# Kodi_Remote.net
KiCad netlist of a schematic drawn in EAGLE
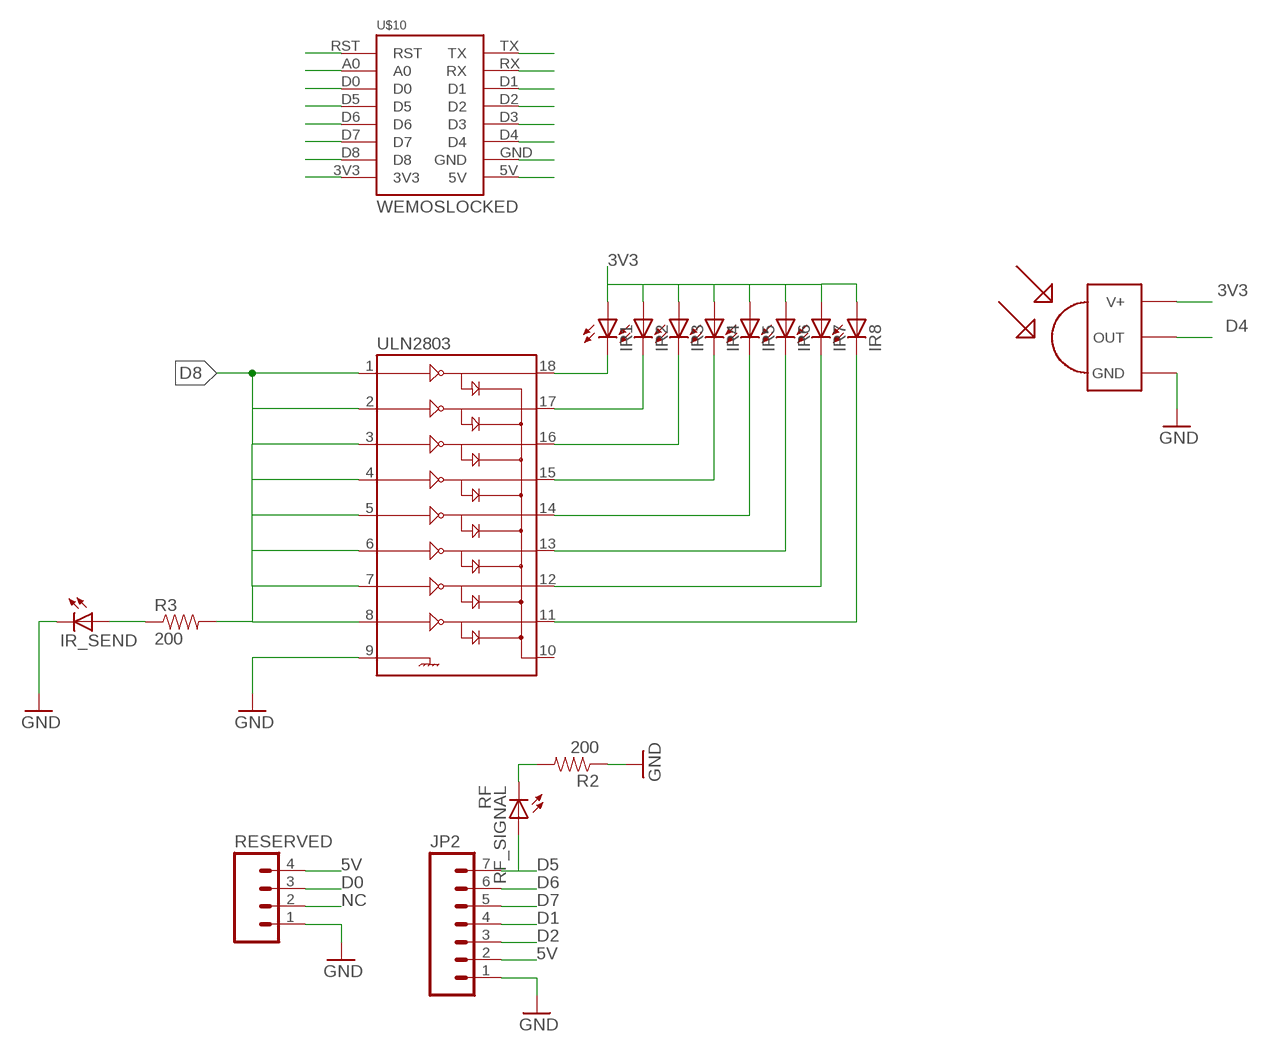
[diagram p0: schematic, sheet 1]

(export (version "E")
  (design (tool "Eeschema 10.0.6"))
  (components
    (comp (ref "IR1")
      (value "LED5MM")
      (footprint "eagle-import:LED5MM")
      (libsource (lib "eagle-import") (part "LED5MM"))
    )
    (comp (ref "IR2")
      (value "LED5MM")
      (footprint "eagle-import:LED5MM")
      (libsource (lib "eagle-import") (part "LED5MM"))
    )
    (comp (ref "IR3")
      (value "LED5MM")
      (footprint "eagle-import:LED5MM")
      (libsource (lib "eagle-import") (part "LED5MM"))
    )
    (comp (ref "IR4")
      (value "LED5MM")
      (footprint "eagle-import:LED5MM")
      (libsource (lib "eagle-import") (part "LED5MM"))
    )
    (comp (ref "IR5")
      (value "LED5MM")
      (footprint "eagle-import:LED5MM")
      (libsource (lib "eagle-import") (part "LED5MM"))
    )
    (comp (ref "IR6")
      (value "LED5MM")
      (footprint "eagle-import:LED5MM")
      (libsource (lib "eagle-import") (part "LED5MM"))
    )
    (comp (ref "IR7")
      (value "LED5MM")
      (footprint "eagle-import:LED5MM")
      (libsource (lib "eagle-import") (part "LED5MM"))
    )
    (comp (ref "IR8")
      (value "LED5MM")
      (footprint "eagle-import:LED5MM")
      (libsource (lib "eagle-import") (part "LED5MM"))
    )
    (comp (ref "IR_SEND")
      (value "LED3MM")
      (footprint "eagle-import:LED3MM")
      (libsource (lib "eagle-import") (part "LED3MM"))
    )
    (comp (ref "JP2")
      (value "M07")
      (footprint "eagle-import:1X07")
      (libsource (lib "eagle-import") (part "M07"))
    )
    (comp (ref "R2")
      (value "200")
      (footprint "eagle-import:0805")
      (libsource (lib "eagle-import") (part "RESISTOR0805-RES"))
    )
    (comp (ref "R3")
      (value "200")
      (footprint "eagle-import:0805")
      (libsource (lib "eagle-import") (part "RESISTOR0805-RES"))
    )
    (comp (ref "RESERVED")
      (value "M04PTH")
      (footprint "eagle-import:1X04")
      (libsource (lib "eagle-import") (part "M04PTH"))
    )
    (comp (ref "RF_SIGNAL")
      (value "RF")
      (footprint "eagle-import:LED3MM")
      (libsource (lib "eagle-import") (part "LED3MM"))
    )
    (comp (ref "TSOP1838")
      (value "TSOP1838")
      (footprint "eagle-import:TSOP18XX")
      (libsource (lib "eagle-import") (part "TSOP1838"))
    )
    (comp (ref "U$10")
      (value "WEMOSLOCKED")
      (footprint "eagle-import:WEMOS_LOCKED")
      (libsource (lib "eagle-import") (part "WEMOSLOCKED"))
    )
    (comp (ref "ULN2803")
      (value "ULN2803DIP")
      (footprint "eagle-import:DIL18")
      (libsource (lib "eagle-import") (part "ULN2803DIP"))
    )
  )
  (nets
    (net (code "1") (name "/3V3") (class "Default")
      (node (ref "IR1") (pin "A") (pinfunction "A_A") (pintype "passive"))
      (node (ref "IR2") (pin "A") (pinfunction "A_A") (pintype "passive"))
      (node (ref "IR3") (pin "A") (pinfunction "A_A") (pintype "passive"))
      (node (ref "IR4") (pin "A") (pinfunction "A_A") (pintype "passive"))
      (node (ref "IR5") (pin "A") (pinfunction "A_A") (pintype "passive"))
      (node (ref "IR6") (pin "A") (pinfunction "A_A") (pintype "passive"))
      (node (ref "IR7") (pin "A") (pinfunction "A_A") (pintype "passive"))
      (node (ref "IR8") (pin "A") (pinfunction "A_A") (pintype "passive"))
      (node (ref "TSOP1838") (pin "VCC") (pinfunction "V+_VCC") (pintype "bidirectional"))
      (node (ref "U$10") (pin "3V3") (pinfunction "3V3_3V3") (pintype "bidirectional"))
    )
    (net (code "2") (name "/5V") (class "Default")
      (node (ref "JP2") (pin "2") (pinfunction "2_2") (pintype "passive"))
      (node (ref "RESERVED") (pin "4") (pinfunction "4_4") (pintype "passive"))
      (node (ref "U$10") (pin "5V") (pinfunction "5V_5V") (pintype "bidirectional"))
    )
    (net (code "3") (name "/D0") (class "Default")
      (node (ref "RESERVED") (pin "3") (pinfunction "3_3") (pintype "passive"))
      (node (ref "U$10") (pin "D0") (pinfunction "D0_D0") (pintype "bidirectional"))
    )
    (net (code "4") (name "/D1") (class "Default")
      (node (ref "JP2") (pin "4") (pinfunction "4_4") (pintype "passive"))
      (node (ref "U$10") (pin "D1") (pinfunction "D1_D1") (pintype "bidirectional"))
    )
    (net (code "5") (name "/D2") (class "Default")
      (node (ref "JP2") (pin "3") (pinfunction "3_3") (pintype "passive"))
      (node (ref "U$10") (pin "D2") (pinfunction "D2_D2") (pintype "bidirectional"))
    )
    (net (code "6") (name "/D4") (class "Default")
      (node (ref "TSOP1838") (pin "OUT") (pinfunction "OUT_OUT") (pintype "bidirectional"))
      (node (ref "U$10") (pin "D4") (pinfunction "D4_D4") (pintype "bidirectional"))
    )
    (net (code "7") (name "/D5") (class "Default")
      (node (ref "JP2") (pin "7") (pinfunction "7_7") (pintype "passive"))
      (node (ref "RF_SIGNAL") (pin "A") (pinfunction "A_A") (pintype "passive"))
      (node (ref "U$10") (pin "D5") (pinfunction "D5_D5") (pintype "bidirectional"))
    )
    (net (code "8") (name "/D6") (class "Default")
      (node (ref "JP2") (pin "6") (pinfunction "6_6") (pintype "passive"))
      (node (ref "U$10") (pin "D6") (pinfunction "D6_D6") (pintype "bidirectional"))
    )
    (net (code "9") (name "/D7") (class "Default")
      (node (ref "JP2") (pin "5") (pinfunction "5_5") (pintype "passive"))
      (node (ref "U$10") (pin "D7") (pinfunction "D7_D7") (pintype "bidirectional"))
    )
    (net (code "10") (name "/NC") (class "Default")
      (node (ref "RESERVED") (pin "2") (pinfunction "2_2") (pintype "passive"))
    )
    (net (code "11") (name "D8") (class "Default")
      (node (ref "R3") (pin "2") (pinfunction "2_2") (pintype "passive"))
      (node (ref "U$10") (pin "D8") (pinfunction "D8_D8") (pintype "bidirectional"))
      (node (ref "ULN2803") (pin "1") (pinfunction "1_1") (pintype "bidirectional"))
      (node (ref "ULN2803") (pin "2") (pinfunction "2_2") (pintype "bidirectional"))
      (node (ref "ULN2803") (pin "3") (pinfunction "3_3") (pintype "bidirectional"))
      (node (ref "ULN2803") (pin "4") (pinfunction "4_4") (pintype "bidirectional"))
      (node (ref "ULN2803") (pin "5") (pinfunction "5_5") (pintype "bidirectional"))
      (node (ref "ULN2803") (pin "6") (pinfunction "6_6") (pintype "bidirectional"))
      (node (ref "ULN2803") (pin "7") (pinfunction "7_7") (pintype "bidirectional"))
      (node (ref "ULN2803") (pin "8") (pinfunction "8_8") (pintype "bidirectional"))
    )
    (net (code "12") (name "GND") (class "Default")
      (node (ref "IR_SEND") (pin "K") (pinfunction "C_K") (pintype "passive"))
      (node (ref "JP2") (pin "1") (pinfunction "1_1") (pintype "passive"))
      (node (ref "R2") (pin "1") (pinfunction "1_1") (pintype "passive"))
      (node (ref "RESERVED") (pin "1") (pinfunction "1_1") (pintype "passive"))
      (node (ref "TSOP1838") (pin "GND") (pinfunction "GND_GND") (pintype "bidirectional"))
      (node (ref "U$10") (pin "GND") (pinfunction "GND_GND") (pintype "bidirectional"))
      (node (ref "ULN2803") (pin "9") (pinfunction "9_9") (pintype "bidirectional"))
    )
    (net (code "13") (name "Net-(IR1-C)") (class "Default")
      (node (ref "IR1") (pin "K") (pinfunction "C_K") (pintype "passive"))
      (node (ref "ULN2803") (pin "18") (pinfunction "18_18") (pintype "bidirectional"))
    )
    (net (code "14") (name "Net-(IR2-C)") (class "Default")
      (node (ref "IR2") (pin "K") (pinfunction "C_K") (pintype "passive"))
      (node (ref "ULN2803") (pin "17") (pinfunction "17_17") (pintype "bidirectional"))
    )
    (net (code "15") (name "Net-(IR3-C)") (class "Default")
      (node (ref "IR3") (pin "K") (pinfunction "C_K") (pintype "passive"))
      (node (ref "ULN2803") (pin "16") (pinfunction "16_16") (pintype "bidirectional"))
    )
    (net (code "16") (name "Net-(IR4-C)") (class "Default")
      (node (ref "IR4") (pin "K") (pinfunction "C_K") (pintype "passive"))
      (node (ref "ULN2803") (pin "15") (pinfunction "15_15") (pintype "bidirectional"))
    )
    (net (code "17") (name "Net-(IR5-C)") (class "Default")
      (node (ref "IR5") (pin "K") (pinfunction "C_K") (pintype "passive"))
      (node (ref "ULN2803") (pin "14") (pinfunction "14_14") (pintype "bidirectional"))
    )
    (net (code "18") (name "Net-(IR6-C)") (class "Default")
      (node (ref "IR6") (pin "K") (pinfunction "C_K") (pintype "passive"))
      (node (ref "ULN2803") (pin "13") (pinfunction "13_13") (pintype "bidirectional"))
    )
    (net (code "19") (name "Net-(IR7-C)") (class "Default")
      (node (ref "IR7") (pin "K") (pinfunction "C_K") (pintype "passive"))
      (node (ref "ULN2803") (pin "12") (pinfunction "12_12") (pintype "bidirectional"))
    )
    (net (code "20") (name "Net-(IR8-C)") (class "Default")
      (node (ref "IR8") (pin "K") (pinfunction "C_K") (pintype "passive"))
      (node (ref "ULN2803") (pin "11") (pinfunction "11_11") (pintype "bidirectional"))
    )
    (net (code "21") (name "Net-(IR_SEND-PadA)") (class "Default")
      (node (ref "IR_SEND") (pin "A") (pinfunction "A_A") (pintype "passive"))
      (node (ref "R3") (pin "1") (pinfunction "1_1") (pintype "passive"))
    )
    (net (code "22") (name "Net-(RF_SIGNAL-C)") (class "Default")
      (node (ref "R2") (pin "2") (pinfunction "2_2") (pintype "passive"))
      (node (ref "RF_SIGNAL") (pin "K") (pinfunction "C_K") (pintype "passive"))
    )
    (net (code "23") (name "unconnected-(U$10-PadA0)") (class "Default")
      (node (ref "U$10") (pin "A0") (pinfunction "A0_A0") (pintype "bidirectional"))
    )
    (net (code "24") (name "unconnected-(U$10-PadD3)") (class "Default")
      (node (ref "U$10") (pin "D3") (pinfunction "D3_D3") (pintype "bidirectional"))
    )
    (net (code "25") (name "unconnected-(U$10-PadRST)") (class "Default")
      (node (ref "U$10") (pin "RST") (pinfunction "RST_RST") (pintype "bidirectional"))
    )
    (net (code "26") (name "unconnected-(U$10-PadRX)") (class "Default")
      (node (ref "U$10") (pin "RX") (pinfunction "RX_RX") (pintype "bidirectional"))
    )
    (net (code "27") (name "unconnected-(U$10-PadTX)") (class "Default")
      (node (ref "U$10") (pin "TX") (pinfunction "TX_TX") (pintype "bidirectional"))
    )
    (net (code "28") (name "unconnected-(ULN2803-Pad10)") (class "Default")
      (node (ref "ULN2803") (pin "10") (pinfunction "10_10") (pintype "bidirectional"))
    )
  )
)
